# EXT_SMART.net
KiCad netlist of a schematic drawn in EAGLE
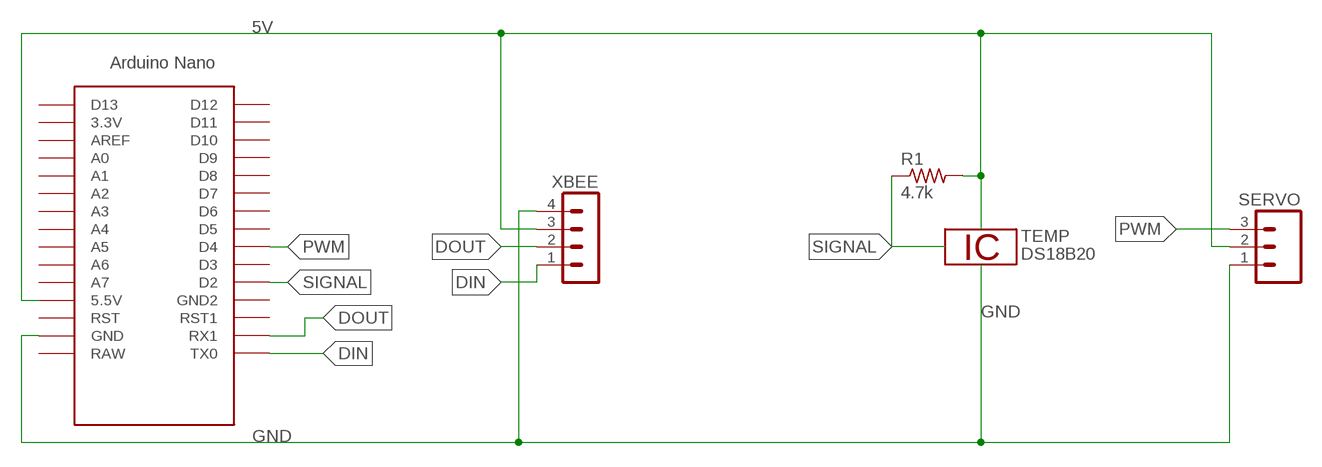
[diagram p0: schematic, sheet 1]

(export (version "E")
  (design (tool "Eeschema 10.0.6"))
  (components
    (comp (ref "R1")
      (value "4.7k")
      (footprint "eagle-import:0204_7")
      (libsource (lib "eagle-import") (part "R-US_0204/7"))
    )
    (comp (ref "SERVO")
      (value "M03")
      (footprint "eagle-import:03P")
      (libsource (lib "eagle-import") (part "M03"))
    )
    (comp (ref "TEMP")
      (value "DS18B20")
      (footprint "eagle-import:TO92-")
      (libsource (lib "eagle-import") (part "DS18B20"))
    )
    (comp (ref "U$1")
      (value "NANO")
      (footprint "eagle-import:NANO")
      (libsource (lib "eagle-import") (part "NANO"))
    )
    (comp (ref "XBEE")
      (value "MA04-1")
      (footprint "eagle-import:MA04-1")
      (libsource (lib "eagle-import") (part "MA04-1"))
    )
  )
  (nets
    (net (code "1") (name "/5V") (class "Default")
      (node (ref "R1") (pin "2") (pinfunction "2_2") (pintype "passive"))
      (node (ref "SERVO") (pin "2") (pinfunction "2_2") (pintype "passive"))
      (node (ref "U$1") (pin "5V") (pinfunction "5.5V_5V") (pintype "bidirectional"))
      (node (ref "XBEE") (pin "3") (pinfunction "3_3") (pintype "passive"))
    )
    (net (code "2") (name "/GND") (class "Default")
      (node (ref "SERVO") (pin "1") (pinfunction "1_1") (pintype "passive"))
      (node (ref "U$1") (pin "GND") (pinfunction "GND_GND") (pintype "bidirectional"))
      (node (ref "XBEE") (pin "4") (pinfunction "4_4") (pintype "passive"))
    )
    (net (code "3") (name "DIN") (class "Default")
      (node (ref "U$1") (pin "TX0") (pinfunction "TX0_TX0") (pintype "bidirectional"))
      (node (ref "XBEE") (pin "1") (pinfunction "1_1") (pintype "passive"))
    )
    (net (code "4") (name "DOUT") (class "Default")
      (node (ref "U$1") (pin "RX1") (pinfunction "RX1_RX1") (pintype "bidirectional"))
      (node (ref "XBEE") (pin "2") (pinfunction "2_2") (pintype "passive"))
    )
    (net (code "5") (name "PWM") (class "Default")
      (node (ref "SERVO") (pin "3") (pinfunction "3_3") (pintype "passive"))
      (node (ref "U$1") (pin "D4") (pinfunction "D4_D4") (pintype "bidirectional"))
    )
    (net (code "6") (name "SIGNAL") (class "Default")
      (node (ref "R1") (pin "1") (pinfunction "1_1") (pintype "passive"))
      (node (ref "U$1") (pin "D2") (pinfunction "D2_D2") (pintype "bidirectional"))
    )
    (net (code "7") (name "unconnected-(U$1-GND2-PadGND1)") (class "Default")
      (node (ref "U$1") (pin "GND1") (pinfunction "GND2_GND1") (pintype "bidirectional"))
    )
    (net (code "8") (name "unconnected-(U$1-Pad3.3V)") (class "Default")
      (node (ref "U$1") (pin "3.3V") (pinfunction "3.3V_3.3V") (pintype "bidirectional"))
    )
    (net (code "9") (name "unconnected-(U$1-PadA0)") (class "Default")
      (node (ref "U$1") (pin "A0") (pinfunction "A0_A0") (pintype "bidirectional"))
    )
    (net (code "10") (name "unconnected-(U$1-PadA1)") (class "Default")
      (node (ref "U$1") (pin "A1") (pinfunction "A1_A1") (pintype "bidirectional"))
    )
    (net (code "11") (name "unconnected-(U$1-PadA2)") (class "Default")
      (node (ref "U$1") (pin "A2") (pinfunction "A2_A2") (pintype "bidirectional"))
    )
    (net (code "12") (name "unconnected-(U$1-PadA3)") (class "Default")
      (node (ref "U$1") (pin "A3") (pinfunction "A3_A3") (pintype "bidirectional"))
    )
    (net (code "13") (name "unconnected-(U$1-PadA4)") (class "Default")
      (node (ref "U$1") (pin "A4") (pinfunction "A4_A4") (pintype "bidirectional"))
    )
    (net (code "14") (name "unconnected-(U$1-PadA5)") (class "Default")
      (node (ref "U$1") (pin "A5") (pinfunction "A5_A5") (pintype "bidirectional"))
    )
    (net (code "15") (name "unconnected-(U$1-PadA6)") (class "Default")
      (node (ref "U$1") (pin "A6") (pinfunction "A6_A6") (pintype "bidirectional"))
    )
    (net (code "16") (name "unconnected-(U$1-PadA7)") (class "Default")
      (node (ref "U$1") (pin "A7") (pinfunction "A7_A7") (pintype "bidirectional"))
    )
    (net (code "17") (name "unconnected-(U$1-PadAREF)") (class "Default")
      (node (ref "U$1") (pin "AREF") (pinfunction "AREF_AREF") (pintype "bidirectional"))
    )
    (net (code "18") (name "unconnected-(U$1-PadD3)") (class "Default")
      (node (ref "U$1") (pin "D3") (pinfunction "D3_D3") (pintype "bidirectional"))
    )
    (net (code "19") (name "unconnected-(U$1-PadD5)") (class "Default")
      (node (ref "U$1") (pin "D5") (pinfunction "D5_D5") (pintype "bidirectional"))
    )
    (net (code "20") (name "unconnected-(U$1-PadD6)") (class "Default")
      (node (ref "U$1") (pin "D6") (pinfunction "D6_D6") (pintype "bidirectional"))
    )
    (net (code "21") (name "unconnected-(U$1-PadD7)") (class "Default")
      (node (ref "U$1") (pin "D7") (pinfunction "D7_D7") (pintype "bidirectional"))
    )
    (net (code "22") (name "unconnected-(U$1-PadD8)") (class "Default")
      (node (ref "U$1") (pin "D8") (pinfunction "D8_D8") (pintype "bidirectional"))
    )
    (net (code "23") (name "unconnected-(U$1-PadD9)") (class "Default")
      (node (ref "U$1") (pin "D9") (pinfunction "D9_D9") (pintype "bidirectional"))
    )
    (net (code "24") (name "unconnected-(U$1-PadD10)") (class "Default")
      (node (ref "U$1") (pin "D10") (pinfunction "D10_D10") (pintype "bidirectional"))
    )
    (net (code "25") (name "unconnected-(U$1-PadD11)") (class "Default")
      (node (ref "U$1") (pin "D11") (pinfunction "D11_D11") (pintype "bidirectional"))
    )
    (net (code "26") (name "unconnected-(U$1-PadD12)") (class "Default")
      (node (ref "U$1") (pin "D12") (pinfunction "D12_D12") (pintype "bidirectional"))
    )
    (net (code "27") (name "unconnected-(U$1-PadD13)") (class "Default")
      (node (ref "U$1") (pin "D13") (pinfunction "D13_D13") (pintype "bidirectional"))
    )
    (net (code "28") (name "unconnected-(U$1-PadICSP1)") (class "Default")
      (node (ref "U$1") (pin "ICSP1") (pinfunction "ICSP1_ICSP1") (pintype "bidirectional"))
    )
    (net (code "29") (name "unconnected-(U$1-PadICSP2)") (class "Default")
      (node (ref "U$1") (pin "ICSP2") (pinfunction "ICSP2_ICSP2") (pintype "bidirectional"))
    )
    (net (code "30") (name "unconnected-(U$1-PadICSP3)") (class "Default")
      (node (ref "U$1") (pin "ICSP3") (pinfunction "ICSP3_ICSP3") (pintype "bidirectional"))
    )
    (net (code "31") (name "unconnected-(U$1-PadICSP4)") (class "Default")
      (node (ref "U$1") (pin "ICSP4") (pinfunction "ICSP4_ICSP4") (pintype "bidirectional"))
    )
    (net (code "32") (name "unconnected-(U$1-PadICSP5)") (class "Default")
      (node (ref "U$1") (pin "ICSP5") (pinfunction "ICSP5_ICSP5") (pintype "bidirectional"))
    )
    (net (code "33") (name "unconnected-(U$1-PadICSP6)") (class "Default")
      (node (ref "U$1") (pin "ICSP6") (pinfunction "ICSP6_ICSP6") (pintype "bidirectional"))
    )
    (net (code "34") (name "unconnected-(U$1-PadRAW)") (class "Default")
      (node (ref "U$1") (pin "RAW") (pinfunction "RAW_RAW") (pintype "bidirectional"))
    )
    (net (code "35") (name "unconnected-(U$1-PadRST)") (class "Default")
      (node (ref "U$1") (pin "RST") (pinfunction "RST_RST") (pintype "bidirectional"))
    )
    (net (code "36") (name "unconnected-(U$1-PadRST1)") (class "Default")
      (node (ref "U$1") (pin "RST1") (pinfunction "RST1_RST1") (pintype "bidirectional"))
    )
  )
)
